# clock-power-module.net
KiCad netlist of a schematic drawn in EAGLE
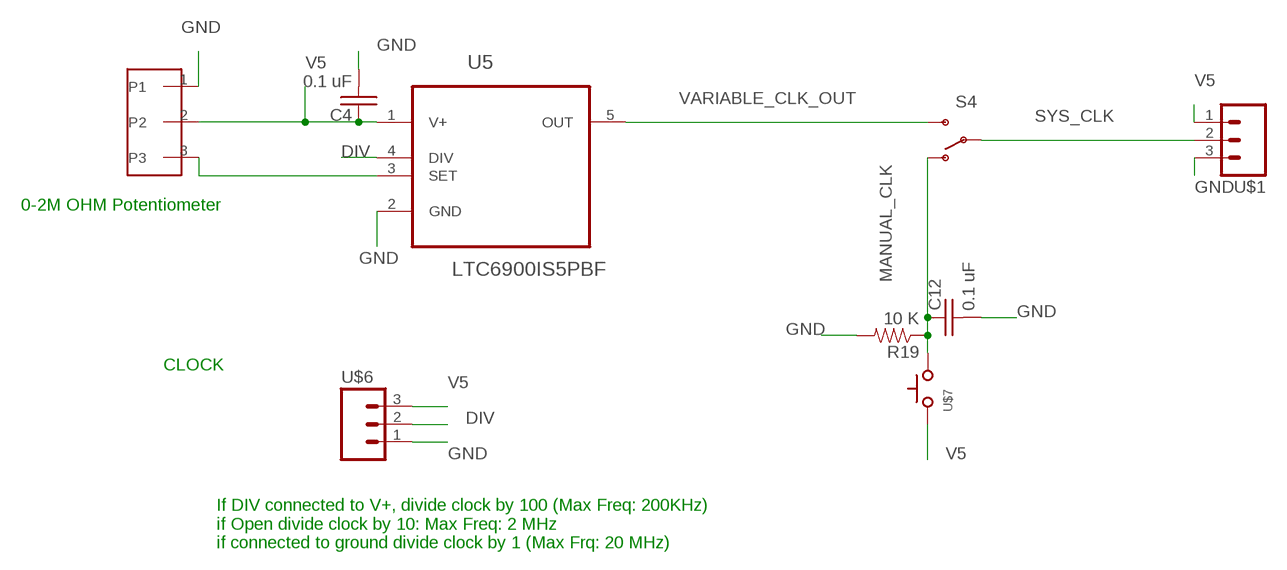
[diagram p0: schematic, sheet 1]
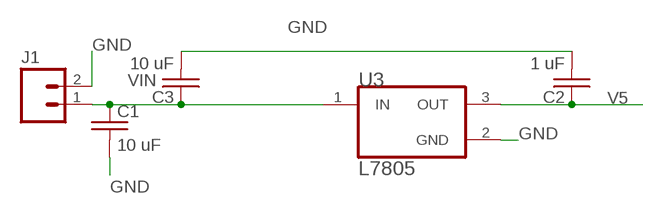
[diagram p1: schematic, sheet 2]

(export (version "E")
  (design (tool "Eeschema 10.0.6"))
  (components
    (comp (ref "C4")
      (value "0.1 uF")
      (footprint "eagle-import:C0805K")
      (libsource (lib "eagle-import") (part "C-USC0805K"))
    )
    (comp (ref "C12")
      (value "0.1 uF")
      (footprint "eagle-import:C0805K")
      (libsource (lib "eagle-import") (part "C-USC0805K"))
    )
    (comp (ref "R19")
      (value "10 K")
      (footprint "eagle-import:0805")
      (libsource (lib "eagle-import") (part "RESISTOR0805-RES"))
    )
    (comp (ref "S4")
      (value "SWITCH-SPSTKIT")
      (footprint "eagle-import:SWITCH-SPDT_KIT")
      (libsource (lib "eagle-import") (part "SWITCH-SPSTKIT"))
    )
    (comp (ref "U$1")
      (value "M03")
      (footprint "eagle-import:1X03_UDPI")
      (libsource (lib "eagle-import") (part "M03"))
    )
    (comp (ref "U$3")
      (value "POTENTIOMETER")
      (footprint "eagle-import:SCREW-TERM-EP")
      (libsource (lib "eagle-import") (part "POTENTIOMETER"))
    )
    (comp (ref "U$6")
      (value "M03")
      (footprint "eagle-import:1X03_UDPI")
      (libsource (lib "eagle-import") (part "M03"))
    )
    (comp (ref "U$7")
      (value "SWITCH_TACTILETACTILE-2PIN-NARROW")
      (footprint "eagle-import:TACTILE-2PIN-NARROW")
      (libsource (lib "eagle-import") (part "SWITCH_TACTILETACTILE-2PIN-NARROW"))
    )
    (comp (ref "U5")
      (value "LTC6900IS5PBF")
      (footprint "eagle-import:SOT95P280X100-5N")
      (fields (field (name "MF") "Linear Technology") (field (name "MP") "LTC6900IS5#PBF"))
      (libsource (lib "eagle-import") (part "LTC6900IS5PBF"))
    )
    (comp (ref "C1")
      (value "10 uF")
      (footprint "eagle-import:C0805K")
      (libsource (lib "eagle-import") (part "C-USC0805K"))
    )
    (comp (ref "C2")
      (value "1 uF")
      (footprint "eagle-import:C0805K")
      (libsource (lib "eagle-import") (part "C-USC0805K"))
    )
    (comp (ref "C3")
      (value "10 uF")
      (footprint "eagle-import:C0805K")
      (libsource (lib "eagle-import") (part "C-USC0805K"))
    )
    (comp (ref "J1")
      (value "M02PTH3")
      (footprint "eagle-import:1X02_LONGPADS")
      (libsource (lib "eagle-import") (part "M02PTH3"))
    )
    (comp (ref "U3")
      (value "L7805")
      (footprint "eagle-import:TO-220-3")
      (fields (field (name "MF") "STMicroelectronics"))
      (libsource (lib "eagle-import") (part "L7805"))
    )
  )
  (nets
    (net (code "1") (name "DIV") (class "Default")
      (node (ref "U$6") (pin "2") (pinfunction "2_2") (pintype "passive"))
      (node (ref "U5") (pin "4") (pinfunction "DIV_4") (pintype "input"))
    )
    (net (code "2") (name "GND") (class "Default")
      (node (ref "C1") (pin "2") (pinfunction "2_2") (pintype "passive"))
      (node (ref "C12") (pin "2") (pinfunction "2_2") (pintype "passive"))
      (node (ref "C2") (pin "2") (pinfunction "2_2") (pintype "passive"))
      (node (ref "C3") (pin "2") (pinfunction "2_2") (pintype "passive"))
      (node (ref "C4") (pin "2") (pinfunction "2_2") (pintype "passive"))
      (node (ref "J1") (pin "2") (pinfunction "2_2") (pintype "passive"))
      (node (ref "R19") (pin "2") (pinfunction "2_2") (pintype "passive"))
      (node (ref "U$1") (pin "3") (pinfunction "3_3") (pintype "passive"))
      (node (ref "U$3") (pin "1") (pinfunction "P1_1") (pintype "bidirectional"))
      (node (ref "U$6") (pin "1") (pinfunction "1_1") (pintype "passive"))
      (node (ref "U3") (pin "2") (pinfunction "GND_2") (pintype "power_in"))
      (node (ref "U5") (pin "2") (pinfunction "GND_2") (pintype "passive"))
    )
    (net (code "3") (name "MANUAL_CLK") (class "Default")
      (node (ref "C12") (pin "1") (pinfunction "1_1") (pintype "passive"))
      (node (ref "R19") (pin "1") (pinfunction "1_1") (pintype "passive"))
      (node (ref "S4") (pin "1") (pinfunction "O_1") (pintype "passive"))
      (node (ref "U$7") (pin "P$1") (pinfunction "A_P$1") (pintype "passive"))
    )
    (net (code "4") (name "Net-(U$3-P3)") (class "Default")
      (node (ref "U$3") (pin "3") (pinfunction "P3_3") (pintype "bidirectional"))
      (node (ref "U5") (pin "3") (pinfunction "SET_3") (pintype "input"))
    )
    (net (code "5") (name "SYS_CLK") (class "Default")
      (node (ref "S4") (pin "2") (pinfunction "P_2") (pintype "passive"))
      (node (ref "U$1") (pin "2") (pinfunction "2_2") (pintype "passive"))
    )
    (net (code "6") (name "V5") (class "Default")
      (node (ref "C2") (pin "1") (pinfunction "1_1") (pintype "passive"))
      (node (ref "C4") (pin "1") (pinfunction "1_1") (pintype "passive"))
      (node (ref "U$1") (pin "1") (pinfunction "1_1") (pintype "passive"))
      (node (ref "U$3") (pin "2") (pinfunction "P2_2") (pintype "bidirectional"))
      (node (ref "U$6") (pin "3") (pinfunction "3_3") (pintype "passive"))
      (node (ref "U$7") (pin "P$2") (pinfunction "C_P$2") (pintype "passive"))
      (node (ref "U3") (pin "3") (pinfunction "OUT_3") (pintype "output"))
      (node (ref "U5") (pin "1") (pinfunction "V+_1") (pintype "power_in"))
    )
    (net (code "7") (name "VARIABLE_CLK_OUT") (class "Default")
      (node (ref "S4") (pin "3") (pinfunction "S_3") (pintype "passive"))
      (node (ref "U5") (pin "5") (pinfunction "OUT_5") (pintype "output"))
    )
    (net (code "8") (name "VIN") (class "Default")
      (node (ref "C1") (pin "1") (pinfunction "1_1") (pintype "passive"))
      (node (ref "C3") (pin "1") (pinfunction "1_1") (pintype "passive"))
      (node (ref "J1") (pin "1") (pinfunction "1_1") (pintype "passive"))
      (node (ref "U3") (pin "1") (pinfunction "IN_1") (pintype "input"))
    )
  )
)
